# Protection_Circuit_5V.net
KiCad netlist of a schematic drawn in Altium Designer
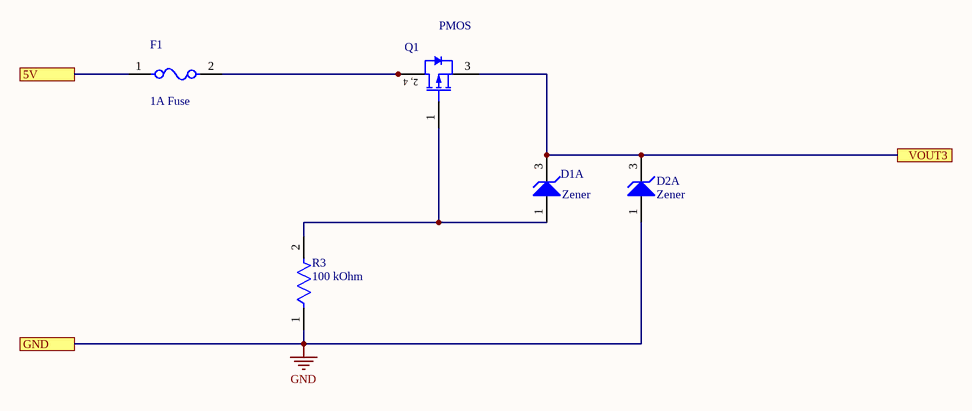
[diagram p0: Protection Circuit 5V.SchDoc]

(export (version "E")
  (design (tool "Eeschema 10.0.6"))
  (components
    (comp (ref "D1")
      (value "Zener")
      (footprint "ONSC-SOT-23-3-318-08_V")
      (description "Zener Voltage Regulator, 225 mW, 3-Pin SOT-23, Pb-Free, Tape and Reel")
      (fields (field (name "PARTNUMBER") "MMBZ5245BLT3G") (field (name "MANUFACTURER") "On Semiconductor"))
      (libsource (lib "Altium Content Vault") (part "ONSC-A1K3-3"))
    )
    (comp (ref "D2")
      (value "Zener")
      (footprint "ONSC-SOT-23-3-318-08_V")
      (description "Zener Voltage Regulator, 225 mW, 3-Pin SOT-23, Pb-Free, Tape and Reel")
      (fields (field (name "PARTNUMBER") "SZBZX84C39ET1G") (field (name "MANUFACTURER") "On Semiconductor"))
      (libsource (lib "Altium Content Vault") (part "ONSC-A1K3-3"))
    )
    (comp (ref "F1")
      (value "1A Fuse")
      (footprint "FP-0603SFS-MFG")
      (description "FUSE BOARD MOUNT 1A 32VDC 0603")
      (fields
        (field (name "OCTOPART") "https://octopart.com/0603sfs100f%2F32-2-littelfuse-74214378")
        (field (name "MANUFACTURER PART NUMBER") "0603SFS100F/32-2")
      )
      (libsource (lib "Altium Content Vault") (part "5bcf9b9f640e542cf0359d10258e979"))
    )
    (comp (ref "Q1")
      (value "PMOS")
      (footprint "FAIR-SOT223-4_V")
      (fields (field (name "MANUFACTURER") "Fairchild Semiconductor"))
      (libsource (lib "Altium Content Vault") (part "PEMOS-GDSD-4"))
    )
    (comp (ref "R3")
      (value "100 kOhm")
      (footprint "FP-CR0805-MFG")
      (description "Thick Film Chip Resistors 0805 100kΩ 0.125W 5% 200ppm/°C")
      (fields (field (name "TOLERANCE") "5%"))
      (libsource (lib "Altium Content Vault") (part "1029c3af85768c4190bb7ad29bc67b5"))
    )
  )
  (nets
    (net (code "1") (name "/5V") (class "Default")
      (node (ref "F1") (pin "1") (pinfunction "1_1") (pintype "passive"))
    )
    (net (code "2") (name "/VOUT3") (class "Default")
      (node (ref "D1") (pin "3") (pinfunction "K_3") (pintype "passive"))
      (node (ref "D2") (pin "3") (pinfunction "K_3") (pintype "passive"))
      (node (ref "Q1") (pin "3") (pinfunction "SOURCE_3") (pintype "passive"))
    )
    (net (code "3") (name "GND") (class "Default")
      (node (ref "D2") (pin "1") (pinfunction "A_1") (pintype "passive"))
      (node (ref "R3") (pin "1") (pinfunction "1_1") (pintype "passive"))
    )
    (net (code "4") (name "Net-(D1A-A)") (class "Default")
      (node (ref "D1") (pin "1") (pinfunction "A_1") (pintype "passive"))
      (node (ref "Q1") (pin "1") (pinfunction "GATE_1") (pintype "passive"))
      (node (ref "R3") (pin "2") (pinfunction "2_2") (pintype "passive"))
    )
    (net (code "5") (name "Net-(F1-Pad2)") (class "Default")
      (node (ref "F1") (pin "2") (pinfunction "2_2") (pintype "passive"))
      (node (ref "Q1") (pin "2") (pinfunction "DRAIN_2") (pintype "passive"))
      (node (ref "Q1") (pin "4") (pinfunction "DRAIN_4") (pintype "passive"))
    )
  )
)
